# Atmega2560.net
KiCad netlist of a schematic drawn in Altium Designer
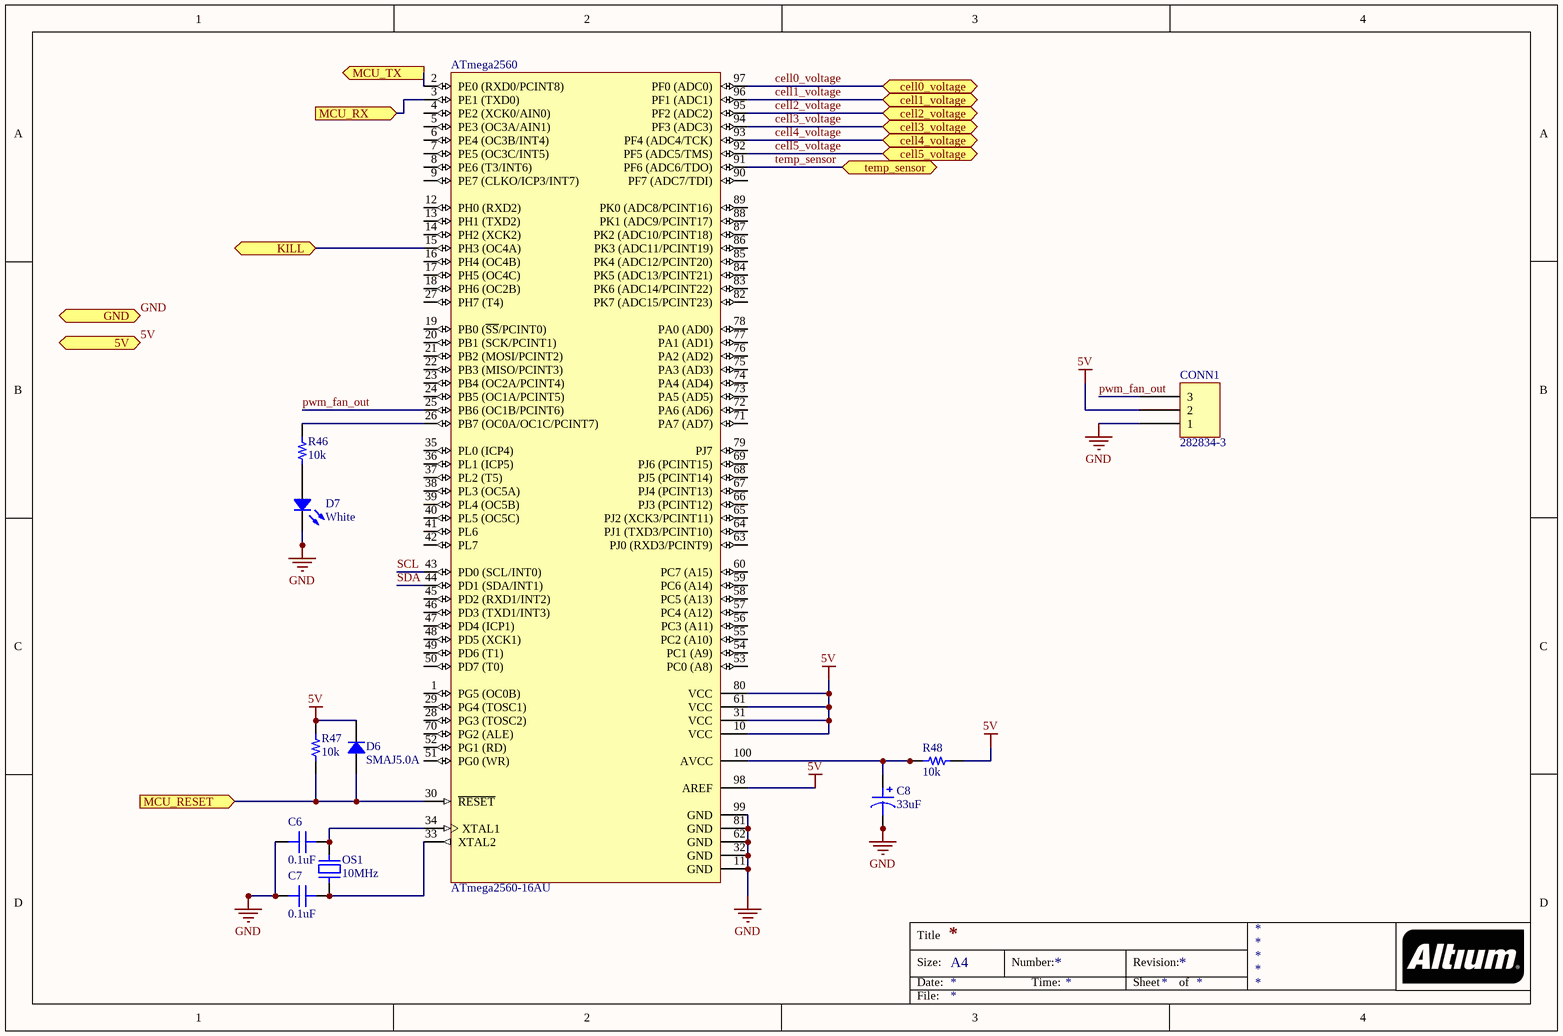
[diagram p0: Atmega2560.SchDoc]

(export (version "E")
  (design (tool "Eeschema 10.0.6"))
  (components
    (comp (ref "ATmega2560")
      (value "ATmega2560-16AU")
      (footprint "100A_N")
      (fields (field (name "PUBLISHER") "Altium Limited"))
      (libsource (lib "Atmel Microcontroller 8-Bit megaAVR") (part "ATmega2560-16AU"))
    )
    (comp (ref "C6")
      (value "0.1uF")
      (footprint "CAP 0402/1005")
      (description "CAP CER 0.1UF 16V X7R 0402")
      (fields
        (field (name "PART NUMBER") "C1005X7R1C104K050BC")
        (field (name "MANUFACTURER") "TDK Corporation")
      )
      (libsource (lib "Celestial Library Database") (part "Capacitor"))
    )
    (comp (ref "C7")
      (value "0.1uF")
      (footprint "CAP 0402/1005")
      (description "CAP CER 0.1UF 16V X7R 0402")
      (fields
        (field (name "PART NUMBER") "C1005X7R1C104K050BC")
        (field (name "MANUFACTURER") "TDK Corporation")
      )
      (libsource (lib "Celestial Library Database") (part "Capacitor"))
    )
    (comp (ref "C8")
      (value "33uF")
      (footprint "CAP ALUM 6.6MM")
      (description "CAP ALUM 33UF 20% 16V SMD")
      (fields (field (name "PART NUMBER") "UWX1C330MCL1GB") (field (name "MANUFACTURER") "Nichicon"))
      (libsource (lib "Celestial Library Database") (part "Polarised Capacitor"))
    )
    (comp (ref "CONN1")
      (value "282834-3")
      (footprint "TE 282834-3")
      (description "TERM BLOCK 3POS SIDE ENT 2.54MM")
      (fields (field (name "MANUFACTURER") "TE Connectivity AMP Connectors") (field (name "VOLTAGE") "150V"))
      (libsource (lib "Celestial Library Database") (part "3 Pin"))
    )
    (comp (ref "D6")
      (value "SMAJ5.0A")
      (footprint "DO214AC SMA")
      (description "TVS DIODE 5VWM 9.2VC SMA")
      (fields (field (name "MANUFACTURER") "Littelfuse Inc."))
      (libsource (lib "Celestial Library Database") (part "Diode"))
    )
    (comp (ref "D7")
      (value "White")
      (footprint "LED 0603/1608")
      (description "LED WHITE 0603 SMD")
      (fields (field (name "PART NUMBER") "LTW-C191TS5") (field (name "MANUFACTURER") "Lite-On Inc."))
      (libsource (lib "Celestial Library Database") (part "LED"))
    )
    (comp (ref "OS1")
      (value "10MHz")
      (footprint "NDK NX5032GA")
      (description "CRYSTAL 10.0000MHZ 8PF SMD")
      (fields (field (name "PART NUMBER") "NX5032GA-10.000M-STD-CSU-1") (field (name "MANUFACTURER") "NDK"))
      (libsource (lib "Celestial Library Database") (part "NDK Crystal NX5032GA"))
    )
    (comp (ref "R46")
      (value "10k")
      (footprint "RES 0402/1005")
      (description "RES SMD 10K OHM 1% 1/10W 0402")
      (fields
        (field (name "PART NUMBER") "ERJ-2RKF1002X")
        (field (name "MANUFACTURER") "Panasonic Electronic Components")
      )
      (libsource (lib "Celestial Library Database") (part "Resistor"))
    )
    (comp (ref "R47")
      (value "10k")
      (footprint "RES 0402/1005")
      (description "RES SMD 10K OHM 1% 1/10W 0402")
      (fields
        (field (name "PART NUMBER") "ERJ-2RKF1002X")
        (field (name "MANUFACTURER") "Panasonic Electronic Components")
      )
      (libsource (lib "Celestial Library Database") (part "Resistor"))
    )
    (comp (ref "R48")
      (value "10k")
      (footprint "RES 0402/1005")
      (description "RES SMD 10K OHM 1% 1/10W 0402")
      (fields
        (field (name "PART NUMBER") "ERJ-2RKF1002X")
        (field (name "MANUFACTURER") "Panasonic Electronic Components")
      )
      (libsource (lib "Celestial Library Database") (part "Resistor"))
    )
  )
  (nets
    (net (code "1") (name "/KILL") (class "Default")
      (node (ref "ATmega2560") (pin "15") (pinfunction "PH3_(OC4A)_15") (pintype "bidirectional"))
    )
    (net (code "2") (name "/MCU_RESET") (class "Default")
      (node (ref "ATmega2560") (pin "30") (pinfunction "~{RESET}_30") (pintype "input"))
      (node (ref "D6") (pin "1") (pinfunction "1_1") (pintype "passive"))
      (node (ref "R47") (pin "1") (pinfunction "1_1") (pintype "passive"))
    )
    (net (code "3") (name "/MCU_RX") (class "Default")
      (node (ref "ATmega2560") (pin "3") (pinfunction "PE1_(TXD0)_3") (pintype "bidirectional"))
    )
    (net (code "4") (name "/MCU_TX") (class "Default")
      (node (ref "ATmega2560") (pin "2") (pinfunction "PE0_(RXD0/PCINT8)_2") (pintype "bidirectional"))
    )
    (net (code "5") (name "/SCL") (class "Default")
      (node (ref "ATmega2560") (pin "43") (pinfunction "PD0_(SCL/INT0)_43") (pintype "bidirectional"))
    )
    (net (code "6") (name "/SDA") (class "Default")
      (node (ref "ATmega2560") (pin "44") (pinfunction "PD1_(SDA/INT1)_44") (pintype "bidirectional"))
    )
    (net (code "7") (name "/cell0_voltage") (class "Default")
      (node (ref "ATmega2560") (pin "97") (pinfunction "PF0_(ADC0)_97") (pintype "bidirectional"))
    )
    (net (code "8") (name "/cell1_voltage") (class "Default")
      (node (ref "ATmega2560") (pin "96") (pinfunction "PF1_(ADC1)_96") (pintype "bidirectional"))
    )
    (net (code "9") (name "/cell2_voltage") (class "Default")
      (node (ref "ATmega2560") (pin "95") (pinfunction "PF2_(ADC2)_95") (pintype "bidirectional"))
    )
    (net (code "10") (name "/cell3_voltage") (class "Default")
      (node (ref "ATmega2560") (pin "94") (pinfunction "PF3_(ADC3)_94") (pintype "bidirectional"))
    )
    (net (code "11") (name "/cell4_voltage") (class "Default")
      (node (ref "ATmega2560") (pin "93") (pinfunction "PF4_(ADC4/TCK)_93") (pintype "bidirectional"))
    )
    (net (code "12") (name "/cell5_voltage") (class "Default")
      (node (ref "ATmega2560") (pin "92") (pinfunction "PF5_(ADC5/TMS)_92") (pintype "bidirectional"))
    )
    (net (code "13") (name "/pwm_fan_out") (class "Default")
      (node (ref "ATmega2560") (pin "25") (pinfunction "PB6_(OC1B/PCINT6)_25") (pintype "bidirectional"))
      (node (ref "CONN1") (pin "3") (pinfunction "3_3") (pintype "passive"))
    )
    (net (code "14") (name "/temp_sensor") (class "Default")
      (node (ref "ATmega2560") (pin "91") (pinfunction "PF6_(ADC6/TDO)_91") (pintype "bidirectional"))
    )
    (net (code "15") (name "5V") (class "Default")
      (node (ref "ATmega2560") (pin "10") (pinfunction "VCC_10") (pintype "power_in"))
      (node (ref "ATmega2560") (pin "31") (pinfunction "VCC_31") (pintype "power_in"))
      (node (ref "ATmega2560") (pin "61") (pinfunction "VCC_61") (pintype "power_in"))
      (node (ref "ATmega2560") (pin "80") (pinfunction "VCC_80") (pintype "power_in"))
      (node (ref "ATmega2560") (pin "98") (pinfunction "AREF_98") (pintype "power_in"))
      (node (ref "CONN1") (pin "2") (pinfunction "2_2") (pintype "passive"))
      (node (ref "D6") (pin "2") (pinfunction "2_2") (pintype "passive"))
      (node (ref "R47") (pin "2") (pinfunction "2_2") (pintype "passive"))
      (node (ref "R48") (pin "2") (pinfunction "2_2") (pintype "passive"))
    )
    (net (code "16") (name "GND") (class "Default")
      (node (ref "ATmega2560") (pin "11") (pinfunction "GND_11") (pintype "power_in"))
      (node (ref "ATmega2560") (pin "32") (pinfunction "GND_32") (pintype "power_in"))
      (node (ref "ATmega2560") (pin "62") (pinfunction "GND_62") (pintype "power_in"))
      (node (ref "ATmega2560") (pin "81") (pinfunction "GND_81") (pintype "power_in"))
      (node (ref "ATmega2560") (pin "99") (pinfunction "GND_99") (pintype "power_in"))
      (node (ref "C6") (pin "2") (pinfunction "2_2") (pintype "passive"))
      (node (ref "C7") (pin "2") (pinfunction "2_2") (pintype "passive"))
      (node (ref "C8") (pin "2") (pinfunction "2_2") (pintype "passive"))
      (node (ref "CONN1") (pin "1") (pinfunction "1_1") (pintype "passive"))
      (node (ref "D7") (pin "2") (pinfunction "2_2") (pintype "passive"))
    )
    (net (code "17") (name "Net-(ATmega2560-AVCC)") (class "Default")
      (node (ref "ATmega2560") (pin "100") (pinfunction "AVCC_100") (pintype "power_in"))
      (node (ref "C8") (pin "1") (pinfunction "1_1") (pintype "passive"))
      (node (ref "R48") (pin "1") (pinfunction "1_1") (pintype "passive"))
    )
    (net (code "18") (name "Net-(ATmega2560-PB7_(OC0A{slash}OC1C{slash}PCINT7))") (class "Default")
      (node (ref "ATmega2560") (pin "26") (pinfunction "PB7_(OC0A/OC1C/PCINT7)_26") (pintype "bidirectional"))
      (node (ref "R46") (pin "2") (pinfunction "2_2") (pintype "passive"))
    )
    (net (code "19") (name "Net-(ATmega2560-XTAL1)") (class "Default")
      (node (ref "ATmega2560") (pin "34") (pinfunction "XTAL1_34") (pintype "input"))
      (node (ref "C6") (pin "1") (pinfunction "1_1") (pintype "passive"))
      (node (ref "OS1") (pin "2") (pinfunction "2_2") (pintype "passive"))
    )
    (net (code "20") (name "Net-(ATmega2560-XTAL2)") (class "Default")
      (node (ref "ATmega2560") (pin "33") (pinfunction "XTAL2_33") (pintype "output"))
      (node (ref "C7") (pin "1") (pinfunction "1_1") (pintype "passive"))
      (node (ref "OS1") (pin "1") (pinfunction "1_1") (pintype "passive"))
    )
    (net (code "21") (name "Net-(D7-Pad1)") (class "Default")
      (node (ref "D7") (pin "1") (pinfunction "1_1") (pintype "passive"))
      (node (ref "R46") (pin "1") (pinfunction "1_1") (pintype "passive"))
    )
    (net (code "22") (name "unconnected-(ATmega2560-PA0_(AD0)-Pad78)") (class "Default")
      (node (ref "ATmega2560") (pin "78") (pinfunction "PA0_(AD0)_78") (pintype "bidirectional"))
    )
    (net (code "23") (name "unconnected-(ATmega2560-PA1_(AD1)-Pad77)") (class "Default")
      (node (ref "ATmega2560") (pin "77") (pinfunction "PA1_(AD1)_77") (pintype "bidirectional"))
    )
    (net (code "24") (name "unconnected-(ATmega2560-PA2_(AD2)-Pad76)") (class "Default")
      (node (ref "ATmega2560") (pin "76") (pinfunction "PA2_(AD2)_76") (pintype "bidirectional"))
    )
    (net (code "25") (name "unconnected-(ATmega2560-PA3_(AD3)-Pad75)") (class "Default")
      (node (ref "ATmega2560") (pin "75") (pinfunction "PA3_(AD3)_75") (pintype "bidirectional"))
    )
    (net (code "26") (name "unconnected-(ATmega2560-PA4_(AD4)-Pad74)") (class "Default")
      (node (ref "ATmega2560") (pin "74") (pinfunction "PA4_(AD4)_74") (pintype "bidirectional"))
    )
    (net (code "27") (name "unconnected-(ATmega2560-PA5_(AD5)-Pad73)") (class "Default")
      (node (ref "ATmega2560") (pin "73") (pinfunction "PA5_(AD5)_73") (pintype "bidirectional"))
    )
    (net (code "28") (name "unconnected-(ATmega2560-PA6_(AD6)-Pad72)") (class "Default")
      (node (ref "ATmega2560") (pin "72") (pinfunction "PA6_(AD6)_72") (pintype "bidirectional"))
    )
    (net (code "29") (name "unconnected-(ATmega2560-PA7_(AD7)-Pad71)") (class "Default")
      (node (ref "ATmega2560") (pin "71") (pinfunction "PA7_(AD7)_71") (pintype "bidirectional"))
    )
    (net (code "30") (name "unconnected-(ATmega2560-PB0_(~{SS}{slash}PCINT0)-Pad19)") (class "Default")
      (node (ref "ATmega2560") (pin "19") (pinfunction "PB0_(~{SS}/PCINT0)_19") (pintype "bidirectional"))
    )
    (net (code "31") (name "unconnected-(ATmega2560-PB1_(SCK{slash}PCINT1)-Pad20)") (class "Default")
      (node (ref "ATmega2560") (pin "20") (pinfunction "PB1_(SCK/PCINT1)_20") (pintype "bidirectional"))
    )
    (net (code "32") (name "unconnected-(ATmega2560-PB2_(MOSI{slash}PCINT2)-Pad21)") (class "Default")
      (node (ref "ATmega2560") (pin "21") (pinfunction "PB2_(MOSI/PCINT2)_21") (pintype "bidirectional"))
    )
    (net (code "33") (name "unconnected-(ATmega2560-PB3_(MISO{slash}PCINT3)-Pad22)") (class "Default")
      (node (ref "ATmega2560") (pin "22") (pinfunction "PB3_(MISO/PCINT3)_22") (pintype "bidirectional"))
    )
    (net (code "34") (name "unconnected-(ATmega2560-PB4_(OC2A{slash}PCINT4)-Pad23)") (class "Default")
      (node (ref "ATmega2560") (pin "23") (pinfunction "PB4_(OC2A/PCINT4)_23") (pintype "bidirectional"))
    )
    (net (code "35") (name "unconnected-(ATmega2560-PB5_(OC1A{slash}PCINT5)-Pad24)") (class "Default")
      (node (ref "ATmega2560") (pin "24") (pinfunction "PB5_(OC1A/PCINT5)_24") (pintype "bidirectional"))
    )
    (net (code "36") (name "unconnected-(ATmega2560-PC0_(A8)-Pad53)") (class "Default")
      (node (ref "ATmega2560") (pin "53") (pinfunction "PC0_(A8)_53") (pintype "bidirectional"))
    )
    (net (code "37") (name "unconnected-(ATmega2560-PC1_(A9)-Pad54)") (class "Default")
      (node (ref "ATmega2560") (pin "54") (pinfunction "PC1_(A9)_54") (pintype "bidirectional"))
    )
    (net (code "38") (name "unconnected-(ATmega2560-PC2_(A10)-Pad55)") (class "Default")
      (node (ref "ATmega2560") (pin "55") (pinfunction "PC2_(A10)_55") (pintype "bidirectional"))
    )
    (net (code "39") (name "unconnected-(ATmega2560-PC3_(A11)-Pad56)") (class "Default")
      (node (ref "ATmega2560") (pin "56") (pinfunction "PC3_(A11)_56") (pintype "bidirectional"))
    )
    (net (code "40") (name "unconnected-(ATmega2560-PC4_(A12)-Pad57)") (class "Default")
      (node (ref "ATmega2560") (pin "57") (pinfunction "PC4_(A12)_57") (pintype "bidirectional"))
    )
    (net (code "41") (name "unconnected-(ATmega2560-PC5_(A13)-Pad58)") (class "Default")
      (node (ref "ATmega2560") (pin "58") (pinfunction "PC5_(A13)_58") (pintype "bidirectional"))
    )
    (net (code "42") (name "unconnected-(ATmega2560-PC6_(A14)-Pad59)") (class "Default")
      (node (ref "ATmega2560") (pin "59") (pinfunction "PC6_(A14)_59") (pintype "bidirectional"))
    )
    (net (code "43") (name "unconnected-(ATmega2560-PC7_(A15)-Pad60)") (class "Default")
      (node (ref "ATmega2560") (pin "60") (pinfunction "PC7_(A15)_60") (pintype "bidirectional"))
    )
    (net (code "44") (name "unconnected-(ATmega2560-PD2_(RXD1{slash}INT2)-Pad45)") (class "Default")
      (node (ref "ATmega2560") (pin "45") (pinfunction "PD2_(RXD1/INT2)_45") (pintype "bidirectional"))
    )
    (net (code "45") (name "unconnected-(ATmega2560-PD3_(TXD1{slash}INT3)-Pad46)") (class "Default")
      (node (ref "ATmega2560") (pin "46") (pinfunction "PD3_(TXD1/INT3)_46") (pintype "bidirectional"))
    )
    (net (code "46") (name "unconnected-(ATmega2560-PD4_(ICP1)-Pad47)") (class "Default")
      (node (ref "ATmega2560") (pin "47") (pinfunction "PD4_(ICP1)_47") (pintype "bidirectional"))
    )
    (net (code "47") (name "unconnected-(ATmega2560-PD5_(XCK1)-Pad48)") (class "Default")
      (node (ref "ATmega2560") (pin "48") (pinfunction "PD5_(XCK1)_48") (pintype "bidirectional"))
    )
    (net (code "48") (name "unconnected-(ATmega2560-PD6_(T1)-Pad49)") (class "Default")
      (node (ref "ATmega2560") (pin "49") (pinfunction "PD6_(T1)_49") (pintype "bidirectional"))
    )
    (net (code "49") (name "unconnected-(ATmega2560-PD7_(T0)-Pad50)") (class "Default")
      (node (ref "ATmega2560") (pin "50") (pinfunction "PD7_(T0)_50") (pintype "bidirectional"))
    )
    (net (code "50") (name "unconnected-(ATmega2560-PE2_(XCK0{slash}AIN0)-Pad4)") (class "Default")
      (node (ref "ATmega2560") (pin "4") (pinfunction "PE2_(XCK0/AIN0)_4") (pintype "bidirectional"))
    )
    (net (code "51") (name "unconnected-(ATmega2560-PE3_(OC3A{slash}AIN1)-Pad5)") (class "Default")
      (node (ref "ATmega2560") (pin "5") (pinfunction "PE3_(OC3A/AIN1)_5") (pintype "bidirectional"))
    )
    (net (code "52") (name "unconnected-(ATmega2560-PE4_(OC3B{slash}INT4)-Pad6)") (class "Default")
      (node (ref "ATmega2560") (pin "6") (pinfunction "PE4_(OC3B/INT4)_6") (pintype "bidirectional"))
    )
    (net (code "53") (name "unconnected-(ATmega2560-PE5_(OC3C{slash}INT5)-Pad7)") (class "Default")
      (node (ref "ATmega2560") (pin "7") (pinfunction "PE5_(OC3C/INT5)_7") (pintype "bidirectional"))
    )
    (net (code "54") (name "unconnected-(ATmega2560-PE6_(T3{slash}INT6)-Pad8)") (class "Default")
      (node (ref "ATmega2560") (pin "8") (pinfunction "PE6_(T3/INT6)_8") (pintype "bidirectional"))
    )
    (net (code "55") (name "unconnected-(ATmega2560-PE7_(CLKO{slash}ICP3{slash}INT7)-Pad9)") (class "Default")
      (node (ref "ATmega2560") (pin "9") (pinfunction "PE7_(CLKO/ICP3/INT7)_9") (pintype "bidirectional"))
    )
    (net (code "56") (name "unconnected-(ATmega2560-PF7_(ADC7{slash}TDI)-Pad90)") (class "Default")
      (node (ref "ATmega2560") (pin "90") (pinfunction "PF7_(ADC7/TDI)_90") (pintype "bidirectional"))
    )
    (net (code "57") (name "unconnected-(ATmega2560-PG0_(WR)-Pad51)") (class "Default")
      (node (ref "ATmega2560") (pin "51") (pinfunction "PG0_(WR)_51") (pintype "bidirectional"))
    )
    (net (code "58") (name "unconnected-(ATmega2560-PG1_(RD)-Pad52)") (class "Default")
      (node (ref "ATmega2560") (pin "52") (pinfunction "PG1_(RD)_52") (pintype "bidirectional"))
    )
    (net (code "59") (name "unconnected-(ATmega2560-PG2_(ALE)-Pad70)") (class "Default")
      (node (ref "ATmega2560") (pin "70") (pinfunction "PG2_(ALE)_70") (pintype "bidirectional"))
    )
    (net (code "60") (name "unconnected-(ATmega2560-PG3_(TOSC2)-Pad28)") (class "Default")
      (node (ref "ATmega2560") (pin "28") (pinfunction "PG3_(TOSC2)_28") (pintype "bidirectional"))
    )
    (net (code "61") (name "unconnected-(ATmega2560-PG4_(TOSC1)-Pad29)") (class "Default")
      (node (ref "ATmega2560") (pin "29") (pinfunction "PG4_(TOSC1)_29") (pintype "bidirectional"))
    )
    (net (code "62") (name "unconnected-(ATmega2560-PG5_(OC0B)-Pad1)") (class "Default")
      (node (ref "ATmega2560") (pin "1") (pinfunction "PG5_(OC0B)_1") (pintype "bidirectional"))
    )
    (net (code "63") (name "unconnected-(ATmega2560-PH0_(RXD2)-Pad12)") (class "Default")
      (node (ref "ATmega2560") (pin "12") (pinfunction "PH0_(RXD2)_12") (pintype "bidirectional"))
    )
    (net (code "64") (name "unconnected-(ATmega2560-PH1_(TXD2)-Pad13)") (class "Default")
      (node (ref "ATmega2560") (pin "13") (pinfunction "PH1_(TXD2)_13") (pintype "bidirectional"))
    )
    (net (code "65") (name "unconnected-(ATmega2560-PH2_(XCK2)-Pad14)") (class "Default")
      (node (ref "ATmega2560") (pin "14") (pinfunction "PH2_(XCK2)_14") (pintype "bidirectional"))
    )
    (net (code "66") (name "unconnected-(ATmega2560-PH4_(OC4B)-Pad16)") (class "Default")
      (node (ref "ATmega2560") (pin "16") (pinfunction "PH4_(OC4B)_16") (pintype "bidirectional"))
    )
    (net (code "67") (name "unconnected-(ATmega2560-PH5_(OC4C)-Pad17)") (class "Default")
      (node (ref "ATmega2560") (pin "17") (pinfunction "PH5_(OC4C)_17") (pintype "bidirectional"))
    )
    (net (code "68") (name "unconnected-(ATmega2560-PH6_(OC2B)-Pad18)") (class "Default")
      (node (ref "ATmega2560") (pin "18") (pinfunction "PH6_(OC2B)_18") (pintype "bidirectional"))
    )
    (net (code "69") (name "unconnected-(ATmega2560-PH7_(T4)-Pad27)") (class "Default")
      (node (ref "ATmega2560") (pin "27") (pinfunction "PH7_(T4)_27") (pintype "bidirectional"))
    )
    (net (code "70") (name "unconnected-(ATmega2560-PJ0_(RXD3{slash}PCINT9)-Pad63)") (class "Default")
      (node (ref "ATmega2560") (pin "63") (pinfunction "PJ0_(RXD3/PCINT9)_63") (pintype "bidirectional"))
    )
    (net (code "71") (name "unconnected-(ATmega2560-PJ1_(TXD3{slash}PCINT10)-Pad64)") (class "Default")
      (node (ref "ATmega2560") (pin "64") (pinfunction "PJ1_(TXD3/PCINT10)_64") (pintype "bidirectional"))
    )
    (net (code "72") (name "unconnected-(ATmega2560-PJ2_(XCK3{slash}PCINT11)-Pad65)") (class "Default")
      (node (ref "ATmega2560") (pin "65") (pinfunction "PJ2_(XCK3/PCINT11)_65") (pintype "bidirectional"))
    )
    (net (code "73") (name "unconnected-(ATmega2560-PJ3_(PCINT12)-Pad66)") (class "Default")
      (node (ref "ATmega2560") (pin "66") (pinfunction "PJ3_(PCINT12)_66") (pintype "bidirectional"))
    )
    (net (code "74") (name "unconnected-(ATmega2560-PJ4_(PCINT13)-Pad67)") (class "Default")
      (node (ref "ATmega2560") (pin "67") (pinfunction "PJ4_(PCINT13)_67") (pintype "bidirectional"))
    )
    (net (code "75") (name "unconnected-(ATmega2560-PJ5_(PCINT14)-Pad68)") (class "Default")
      (node (ref "ATmega2560") (pin "68") (pinfunction "PJ5_(PCINT14)_68") (pintype "bidirectional"))
    )
    (net (code "76") (name "unconnected-(ATmega2560-PJ6_(PCINT15)-Pad69)") (class "Default")
      (node (ref "ATmega2560") (pin "69") (pinfunction "PJ6_(PCINT15)_69") (pintype "bidirectional"))
    )
    (net (code "77") (name "unconnected-(ATmega2560-PJ7-Pad79)") (class "Default")
      (node (ref "ATmega2560") (pin "79") (pinfunction "PJ7_79") (pintype "bidirectional"))
    )
    (net (code "78") (name "unconnected-(ATmega2560-PK0_(ADC8{slash}PCINT16)-Pad89)") (class "Default")
      (node (ref "ATmega2560") (pin "89") (pinfunction "PK0_(ADC8/PCINT16)_89") (pintype "bidirectional"))
    )
    (net (code "79") (name "unconnected-(ATmega2560-PK1_(ADC9{slash}PCINT17)-Pad88)") (class "Default")
      (node (ref "ATmega2560") (pin "88") (pinfunction "PK1_(ADC9/PCINT17)_88") (pintype "bidirectional"))
    )
    (net (code "80") (name "unconnected-(ATmega2560-PK2_(ADC10{slash}PCINT18)-Pad87)") (class "Default")
      (node (ref "ATmega2560") (pin "87") (pinfunction "PK2_(ADC10/PCINT18)_87") (pintype "bidirectional"))
    )
    (net (code "81") (name "unconnected-(ATmega2560-PK3_(ADC11{slash}PCINT19)-Pad86)") (class "Default")
      (node (ref "ATmega2560") (pin "86") (pinfunction "PK3_(ADC11/PCINT19)_86") (pintype "bidirectional"))
    )
    (net (code "82") (name "unconnected-(ATmega2560-PK4_(ADC12{slash}PCINT20)-Pad85)") (class "Default")
      (node (ref "ATmega2560") (pin "85") (pinfunction "PK4_(ADC12/PCINT20)_85") (pintype "bidirectional"))
    )
    (net (code "83") (name "unconnected-(ATmega2560-PK5_(ADC13{slash}PCINT21)-Pad84)") (class "Default")
      (node (ref "ATmega2560") (pin "84") (pinfunction "PK5_(ADC13/PCINT21)_84") (pintype "bidirectional"))
    )
    (net (code "84") (name "unconnected-(ATmega2560-PK6_(ADC14{slash}PCINT22)-Pad83)") (class "Default")
      (node (ref "ATmega2560") (pin "83") (pinfunction "PK6_(ADC14/PCINT22)_83") (pintype "bidirectional"))
    )
    (net (code "85") (name "unconnected-(ATmega2560-PK7_(ADC15{slash}PCINT23)-Pad82)") (class "Default")
      (node (ref "ATmega2560") (pin "82") (pinfunction "PK7_(ADC15/PCINT23)_82") (pintype "bidirectional"))
    )
    (net (code "86") (name "unconnected-(ATmega2560-PL0_(ICP4)-Pad35)") (class "Default")
      (node (ref "ATmega2560") (pin "35") (pinfunction "PL0_(ICP4)_35") (pintype "bidirectional"))
    )
    (net (code "87") (name "unconnected-(ATmega2560-PL1_(ICP5)-Pad36)") (class "Default")
      (node (ref "ATmega2560") (pin "36") (pinfunction "PL1_(ICP5)_36") (pintype "bidirectional"))
    )
    (net (code "88") (name "unconnected-(ATmega2560-PL2_(T5)-Pad37)") (class "Default")
      (node (ref "ATmega2560") (pin "37") (pinfunction "PL2_(T5)_37") (pintype "bidirectional"))
    )
    (net (code "89") (name "unconnected-(ATmega2560-PL3_(OC5A)-Pad38)") (class "Default")
      (node (ref "ATmega2560") (pin "38") (pinfunction "PL3_(OC5A)_38") (pintype "bidirectional"))
    )
    (net (code "90") (name "unconnected-(ATmega2560-PL4_(OC5B)-Pad39)") (class "Default")
      (node (ref "ATmega2560") (pin "39") (pinfunction "PL4_(OC5B)_39") (pintype "bidirectional"))
    )
    (net (code "91") (name "unconnected-(ATmega2560-PL5_(OC5C)-Pad40)") (class "Default")
      (node (ref "ATmega2560") (pin "40") (pinfunction "PL5_(OC5C)_40") (pintype "bidirectional"))
    )
    (net (code "92") (name "unconnected-(ATmega2560-PL6-Pad41)") (class "Default")
      (node (ref "ATmega2560") (pin "41") (pinfunction "PL6_41") (pintype "bidirectional"))
    )
    (net (code "93") (name "unconnected-(ATmega2560-PL7-Pad42)") (class "Default")
      (node (ref "ATmega2560") (pin "42") (pinfunction "PL7_42") (pintype "bidirectional"))
    )
  )
)
